# Sheet1.net
KiCad netlist of a schematic drawn in Altium Designer
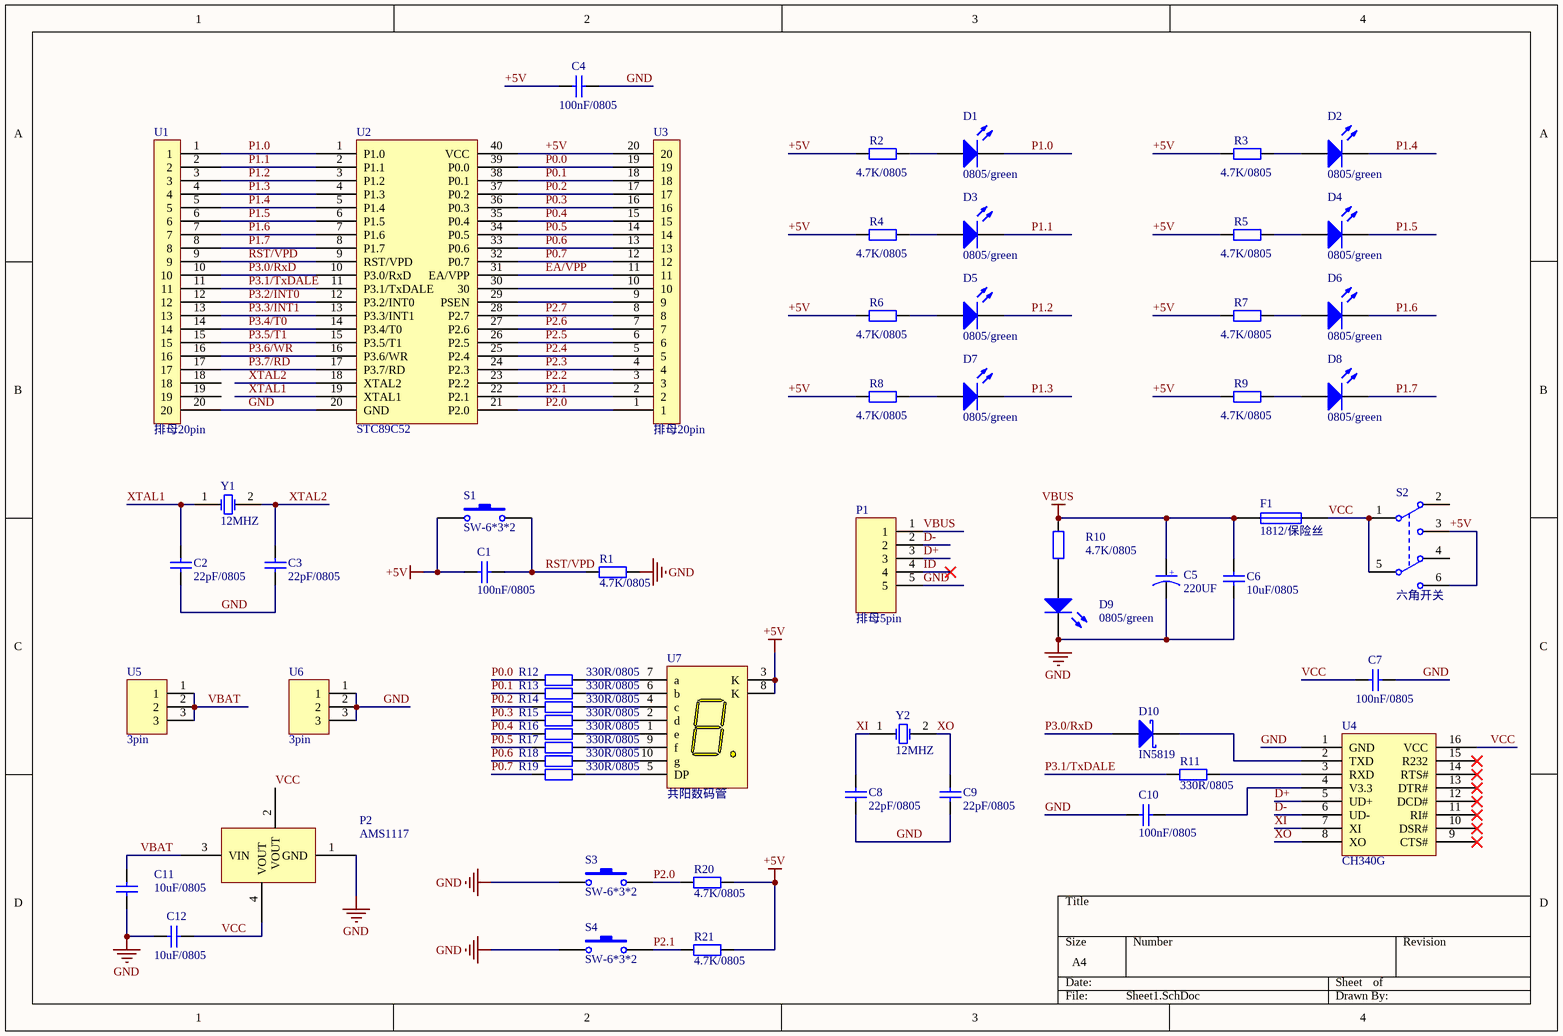
[diagram p0: Sheet1.SchDoc]

(export (version "E")
  (design (tool "Eeschema 10.0.6"))
  (components
    (comp (ref "C1")
      (value "100nF/0805")
      (footprint "C_0805")
      (description "贴片电容")
      (libsource (lib "51最小系统板") (part "Cap1_1"))
    )
    (comp (ref "C2")
      (value "22pF/0805")
      (footprint "C_0805")
      (description "贴片电容")
      (libsource (lib "51最小系统板") (part "Cap1"))
    )
    (comp (ref "C3")
      (value "22pF/0805")
      (footprint "C_0805")
      (description "贴片电容")
      (libsource (lib "51最小系统板") (part "Cap1"))
    )
    (comp (ref "C4")
      (value "100nF/0805")
      (footprint "C_0805")
      (description "贴片电容")
      (libsource (lib "51最小系统板") (part "Cap1_1"))
    )
    (comp (ref "C5")
      (value "220UF")
      (footprint "C-电解电容")
      (description "电解电容")
      (libsource (lib "51最小系统板") (part "Cap2"))
    )
    (comp (ref "C6")
      (value "10uF/0805")
      (footprint "C_0805")
      (description "贴片电容")
      (libsource (lib "51最小系统板") (part "Cap1_1"))
    )
    (comp (ref "C7")
      (value "100nF/0805")
      (footprint "C_0805")
      (description "贴片电容")
      (libsource (lib "51最小系统板") (part "Cap1_1"))
    )
    (comp (ref "C8")
      (value "22pF/0805")
      (footprint "C_0805")
      (description "贴片电容")
      (libsource (lib "51最小系统板") (part "Cap1"))
    )
    (comp (ref "C9")
      (value "22pF/0805")
      (footprint "C_0805")
      (description "贴片电容")
      (libsource (lib "51最小系统板") (part "Cap1"))
    )
    (comp (ref "C10")
      (value "100nF/0805")
      (footprint "C_0805")
      (description "贴片电容")
      (libsource (lib "51最小系统板") (part "Cap1_1"))
    )
    (comp (ref "C11")
      (value "10uF/0805")
      (footprint "C_0805")
      (description "贴片电容")
      (libsource (lib "51最小系统板") (part "Cap1"))
    )
    (comp (ref "C12")
      (value "10uF/0805")
      (footprint "C_0805")
      (description "贴片电容")
      (libsource (lib "51最小系统板") (part "Cap1"))
    )
    (comp (ref "D1")
      (value "0805/green")
      (footprint "LED_0805")
      (description "发光二极管")
      (libsource (lib "51最小系统板") (part "LED"))
    )
    (comp (ref "D2")
      (value "0805/green")
      (footprint "LED_0805")
      (description "发光二极管")
      (libsource (lib "51最小系统板") (part "LED"))
    )
    (comp (ref "D3")
      (value "0805/green")
      (footprint "LED_0805")
      (description "发光二极管")
      (libsource (lib "51最小系统板") (part "LED"))
    )
    (comp (ref "D4")
      (value "0805/green")
      (footprint "LED_0805")
      (description "发光二极管")
      (libsource (lib "51最小系统板") (part "LED"))
    )
    (comp (ref "D5")
      (value "0805/green")
      (footprint "LED_0805")
      (description "发光二极管")
      (libsource (lib "51最小系统板") (part "LED"))
    )
    (comp (ref "D6")
      (value "0805/green")
      (footprint "LED_0805")
      (description "发光二极管")
      (libsource (lib "51最小系统板") (part "LED"))
    )
    (comp (ref "D7")
      (value "0805/green")
      (footprint "LED_0805")
      (description "发光二极管")
      (libsource (lib "51最小系统板") (part "LED"))
    )
    (comp (ref "D8")
      (value "0805/green")
      (footprint "LED_0805")
      (description "发光二极管")
      (libsource (lib "51最小系统板") (part "LED"))
    )
    (comp (ref "D9")
      (value "0805/green")
      (footprint "LED_0805")
      (description "发光二极管")
      (libsource (lib "51最小系统板") (part "LED"))
    )
    (comp (ref "D10")
      (value "IN5819")
      (footprint "D-SMA")
      (description "肖特基二极管")
      (libsource (lib "51最小系统板") (part "Diode_SCHOTTKY"))
    )
    (comp (ref "F1")
      (value "1812/保险丝")
      (footprint "FUSE-1812")
      (description "贴片保险丝")
      (libsource (lib "51最小系统板") (part "FUSE"))
    )
    (comp (ref "P1") (value "排母5pin") (footprint "排母2.54-5PIN") (libsource (lib "51最小系统板") (part "排母5pin")))
    (comp (ref "P2") (value "AMS1117") (footprint "AMS1117") (libsource (lib "51最小系统板") (part "AMS1117")))
    (comp (ref "R1")
      (value "4.7K/0805")
      (footprint "R_0805")
      (description "贴片电阻")
      (libsource (lib "") (part "Res1_1_1"))
    )
    (comp (ref "R2")
      (value "4.7K/0805")
      (footprint "R_0805")
      (description "贴片电阻")
      (libsource (lib "51最小系统板") (part "Res1_1"))
    )
    (comp (ref "R3")
      (value "4.7K/0805")
      (footprint "R_0805")
      (description "贴片电阻")
      (libsource (lib "51最小系统板") (part "Res1_1"))
    )
    (comp (ref "R4")
      (value "4.7K/0805")
      (footprint "R_0805")
      (description "贴片电阻")
      (libsource (lib "51最小系统板") (part "Res1_1"))
    )
    (comp (ref "R5")
      (value "4.7K/0805")
      (footprint "R_0805")
      (description "贴片电阻")
      (libsource (lib "51最小系统板") (part "Res1_1"))
    )
    (comp (ref "R6")
      (value "4.7K/0805")
      (footprint "R_0805")
      (description "贴片电阻")
      (libsource (lib "51最小系统板") (part "Res1_1"))
    )
    (comp (ref "R7")
      (value "4.7K/0805")
      (footprint "R_0805")
      (description "贴片电阻")
      (libsource (lib "51最小系统板") (part "Res1_1"))
    )
    (comp (ref "R8")
      (value "4.7K/0805")
      (footprint "R_0805")
      (description "贴片电阻")
      (libsource (lib "51最小系统板") (part "Res1_1"))
    )
    (comp (ref "R9")
      (value "4.7K/0805")
      (footprint "R_0805")
      (description "贴片电阻")
      (libsource (lib "51最小系统板") (part "Res1_1"))
    )
    (comp (ref "R10")
      (value "4.7K/0805")
      (footprint "R_0805")
      (description "贴片电阻")
      (libsource (lib "") (part "Res1_1_2"))
    )
    (comp (ref "R11")
      (value "330R/0805")
      (footprint "R_0805")
      (description "贴片电阻")
      (libsource (lib "51最小系统板") (part "Res1_1"))
    )
    (comp (ref "R12")
      (value "330R/0805")
      (footprint "R_0805")
      (description "贴片电阻")
      (libsource (lib "") (part "Res1_1_1"))
    )
    (comp (ref "R13")
      (value "330R/0805")
      (footprint "R_0805")
      (description "贴片电阻")
      (libsource (lib "") (part "Res1_1_1"))
    )
    (comp (ref "R14")
      (value "330R/0805")
      (footprint "R_0805")
      (description "贴片电阻")
      (libsource (lib "") (part "Res1_1_1"))
    )
    (comp (ref "R15")
      (value "330R/0805")
      (footprint "R_0805")
      (description "贴片电阻")
      (libsource (lib "") (part "Res1_1_1"))
    )
    (comp (ref "R16")
      (value "330R/0805")
      (footprint "R_0805")
      (description "贴片电阻")
      (libsource (lib "") (part "Res1_1_1"))
    )
    (comp (ref "R17")
      (value "330R/0805")
      (footprint "R_0805")
      (description "贴片电阻")
      (libsource (lib "") (part "Res1_1_1"))
    )
    (comp (ref "R18")
      (value "330R/0805")
      (footprint "R_0805")
      (description "贴片电阻")
      (libsource (lib "") (part "Res1_1_1"))
    )
    (comp (ref "R19")
      (value "330R/0805")
      (footprint "R_0805")
      (description "贴片电阻")
      (libsource (lib "") (part "Res1_1_1"))
    )
    (comp (ref "R20")
      (value "4.7K/0805")
      (footprint "R_0805")
      (description "贴片电阻")
      (libsource (lib "") (part "Res1_1_1"))
    )
    (comp (ref "R21")
      (value "4.7K/0805")
      (footprint "R_0805")
      (description "贴片电阻")
      (libsource (lib "") (part "Res1_1_1"))
    )
    (comp (ref "S1")
      (value "SW-6*3*2")
      (footprint "SW-3*6*2.5")
      (libsource (lib "51最小系统板") (part "SW-6*3*2"))
    )
    (comp (ref "S2") (value "六角开关") (footprint "六角开关7X7") (libsource (lib "51最小系统板") (part "六角开关")))
    (comp (ref "S3")
      (value "SW-6*3*2")
      (footprint "SW-3*6*2.5")
      (libsource (lib "51最小系统板") (part "SW-6*3*2"))
    )
    (comp (ref "S4")
      (value "SW-6*3*2")
      (footprint "SW-3*6*2.5")
      (libsource (lib "51最小系统板") (part "SW-6*3*2"))
    )
    (comp (ref "U1") (value "排母20pin") (footprint "20PIN-2.54") (libsource (lib "51最小系统板") (part "排母20pin")))
    (comp (ref "U2") (value "STC89C52") (footprint "STC89C51") (libsource (lib "51最小系统板") (part "STC89C52")))
    (comp (ref "U3") (value "排母20pin") (footprint "20PIN-2.54") (libsource (lib "") (part "排母20pin_1")))
    (comp (ref "U4") (value "CH340G") (footprint "CH340G") (libsource (lib "51最小系统板") (part "CH340G")))
    (comp (ref "U5") (value "3pin") (footprint "3PIN-2.54") (libsource (lib "51最小系统板") (part "3pin")))
    (comp (ref "U6") (value "3pin") (footprint "3PIN-2.54") (libsource (lib "51最小系统板") (part "3pin")))
    (comp (ref "U7") (value "共阳数码管") (footprint "数码管") (libsource (lib "51最小系统板") (part "共阳数码管")))
    (comp (ref "Y1")
      (value "12MHZ")
      (footprint "HC495")
      (description "二脚无源晶振")
      (libsource (lib "51最小系统板") (part "XTAL_2P"))
    )
    (comp (ref "Y2")
      (value "12MHZ")
      (footprint "HC495")
      (description "二脚无源晶振")
      (libsource (lib "51最小系统板") (part "XTAL_2P"))
    )
  )
  (nets
    (net (code "1") (name "+5V") (class "Default")
      (node (ref "C1") (pin "2") (pinfunction "2_2") (pintype "passive"))
      (node (ref "C4") (pin "2") (pinfunction "2_2") (pintype "passive"))
      (node (ref "R2") (pin "1") (pinfunction "1_1") (pintype "passive"))
      (node (ref "R20") (pin "1") (pinfunction "1_1") (pintype "passive"))
      (node (ref "R21") (pin "1") (pinfunction "1_1") (pintype "passive"))
      (node (ref "R3") (pin "1") (pinfunction "1_1") (pintype "passive"))
      (node (ref "R4") (pin "1") (pinfunction "1_1") (pintype "passive"))
      (node (ref "R5") (pin "1") (pinfunction "1_1") (pintype "passive"))
      (node (ref "R6") (pin "1") (pinfunction "1_1") (pintype "passive"))
      (node (ref "R7") (pin "1") (pinfunction "1_1") (pintype "passive"))
      (node (ref "R8") (pin "1") (pinfunction "1_1") (pintype "passive"))
      (node (ref "R9") (pin "1") (pinfunction "1_1") (pintype "passive"))
      (node (ref "S1") (pin "1") (pinfunction "1_1") (pintype "passive"))
      (node (ref "S2") (pin "3") (pinfunction "NO1_3") (pintype "passive"))
      (node (ref "S2") (pin "6") (pinfunction "NO2_6") (pintype "passive"))
      (node (ref "U2") (pin "40") (pinfunction "VCC_40") (pintype "passive"))
      (node (ref "U3") (pin "20") (pinfunction "20_20") (pintype "passive"))
      (node (ref "U7") (pin "3") (pinfunction "K_3") (pintype "passive"))
      (node (ref "U7") (pin "8") (pinfunction "K_8") (pintype "passive"))
    )
    (net (code "2") (name "/D+") (class "Default")
      (node (ref "P1") (pin "3") (pinfunction "3_3") (pintype "passive"))
      (node (ref "U4") (pin "5") (pinfunction "UD+_5") (pintype "passive"))
    )
    (net (code "3") (name "/D-") (class "Default")
      (node (ref "P1") (pin "2") (pinfunction "2_2") (pintype "passive"))
      (node (ref "U4") (pin "6") (pinfunction "UD-_6") (pintype "passive"))
    )
    (net (code "4") (name "/EA{slash}VPP") (class "Default")
      (node (ref "U2") (pin "31") (pinfunction "EA/VPP_31") (pintype "passive"))
      (node (ref "U3") (pin "11") (pinfunction "11_11") (pintype "passive"))
    )
    (net (code "5") (name "/ID") (class "Default")
      (node (ref "P1") (pin "4") (pinfunction "4_4") (pintype "passive+no_connect"))
    )
    (net (code "6") (name "/P0.0") (class "Default")
      (node (ref "R12") (pin "2") (pinfunction "2_2") (pintype "passive"))
      (node (ref "U2") (pin "39") (pinfunction "P0.0_39") (pintype "passive"))
      (node (ref "U3") (pin "19") (pinfunction "19_19") (pintype "passive"))
    )
    (net (code "7") (name "/P0.1") (class "Default")
      (node (ref "R13") (pin "2") (pinfunction "2_2") (pintype "passive"))
      (node (ref "U2") (pin "38") (pinfunction "P0.1_38") (pintype "passive"))
      (node (ref "U3") (pin "18") (pinfunction "18_18") (pintype "passive"))
    )
    (net (code "8") (name "/P0.2") (class "Default")
      (node (ref "R14") (pin "2") (pinfunction "2_2") (pintype "passive"))
      (node (ref "U2") (pin "37") (pinfunction "P0.2_37") (pintype "passive"))
      (node (ref "U3") (pin "17") (pinfunction "17_17") (pintype "passive"))
    )
    (net (code "9") (name "/P0.3") (class "Default")
      (node (ref "R15") (pin "2") (pinfunction "2_2") (pintype "passive"))
      (node (ref "U2") (pin "36") (pinfunction "P0.3_36") (pintype "passive"))
      (node (ref "U3") (pin "16") (pinfunction "16_16") (pintype "passive"))
    )
    (net (code "10") (name "/P0.4") (class "Default")
      (node (ref "R16") (pin "2") (pinfunction "2_2") (pintype "passive"))
      (node (ref "U2") (pin "35") (pinfunction "P0.4_35") (pintype "passive"))
      (node (ref "U3") (pin "15") (pinfunction "15_15") (pintype "passive"))
    )
    (net (code "11") (name "/P0.5") (class "Default")
      (node (ref "R17") (pin "2") (pinfunction "2_2") (pintype "passive"))
      (node (ref "U2") (pin "34") (pinfunction "P0.5_34") (pintype "passive"))
      (node (ref "U3") (pin "14") (pinfunction "14_14") (pintype "passive"))
    )
    (net (code "12") (name "/P0.6") (class "Default")
      (node (ref "R18") (pin "2") (pinfunction "2_2") (pintype "passive"))
      (node (ref "U2") (pin "33") (pinfunction "P0.6_33") (pintype "passive"))
      (node (ref "U3") (pin "13") (pinfunction "13_13") (pintype "passive"))
    )
    (net (code "13") (name "/P0.7") (class "Default")
      (node (ref "R19") (pin "2") (pinfunction "2_2") (pintype "passive"))
      (node (ref "U2") (pin "32") (pinfunction "P0.7_32") (pintype "passive"))
      (node (ref "U3") (pin "12") (pinfunction "12_12") (pintype "passive"))
    )
    (net (code "14") (name "/P1.0") (class "Default")
      (node (ref "D1") (pin "2") (pinfunction "2_2") (pintype "passive"))
      (node (ref "U1") (pin "1") (pinfunction "1_1") (pintype "passive"))
      (node (ref "U2") (pin "1") (pinfunction "P1.0_1") (pintype "passive"))
    )
    (net (code "15") (name "/P1.1") (class "Default")
      (node (ref "D3") (pin "2") (pinfunction "2_2") (pintype "passive"))
      (node (ref "U1") (pin "2") (pinfunction "2_2") (pintype "passive"))
      (node (ref "U2") (pin "2") (pinfunction "P1.1_2") (pintype "passive"))
    )
    (net (code "16") (name "/P1.2") (class "Default")
      (node (ref "D5") (pin "2") (pinfunction "2_2") (pintype "passive"))
      (node (ref "U1") (pin "3") (pinfunction "3_3") (pintype "passive"))
      (node (ref "U2") (pin "3") (pinfunction "P1.2_3") (pintype "passive"))
    )
    (net (code "17") (name "/P1.3") (class "Default")
      (node (ref "D7") (pin "2") (pinfunction "2_2") (pintype "passive"))
      (node (ref "U1") (pin "4") (pinfunction "4_4") (pintype "passive"))
      (node (ref "U2") (pin "4") (pinfunction "P1.3_4") (pintype "passive"))
    )
    (net (code "18") (name "/P1.4") (class "Default")
      (node (ref "D2") (pin "2") (pinfunction "2_2") (pintype "passive"))
      (node (ref "U1") (pin "5") (pinfunction "5_5") (pintype "passive"))
      (node (ref "U2") (pin "5") (pinfunction "P1.4_5") (pintype "passive"))
    )
    (net (code "19") (name "/P1.5") (class "Default")
      (node (ref "D4") (pin "2") (pinfunction "2_2") (pintype "passive"))
      (node (ref "U1") (pin "6") (pinfunction "6_6") (pintype "passive"))
      (node (ref "U2") (pin "6") (pinfunction "P1.5_6") (pintype "passive"))
    )
    (net (code "20") (name "/P1.6") (class "Default")
      (node (ref "D6") (pin "2") (pinfunction "2_2") (pintype "passive"))
      (node (ref "U1") (pin "7") (pinfunction "7_7") (pintype "passive"))
      (node (ref "U2") (pin "7") (pinfunction "P1.6_7") (pintype "passive"))
    )
    (net (code "21") (name "/P1.7") (class "Default")
      (node (ref "D8") (pin "2") (pinfunction "2_2") (pintype "passive"))
      (node (ref "U1") (pin "8") (pinfunction "8_8") (pintype "passive"))
      (node (ref "U2") (pin "8") (pinfunction "P1.7_8") (pintype "passive"))
    )
    (net (code "22") (name "/P2.0") (class "Default")
      (node (ref "R20") (pin "2") (pinfunction "2_2") (pintype "passive"))
      (node (ref "S3") (pin "2") (pinfunction "2_2") (pintype "passive"))
      (node (ref "U2") (pin "21") (pinfunction "P2.0_21") (pintype "passive"))
      (node (ref "U3") (pin "1") (pinfunction "1_1") (pintype "passive"))
    )
    (net (code "23") (name "/P2.1") (class "Default")
      (node (ref "R21") (pin "2") (pinfunction "2_2") (pintype "passive"))
      (node (ref "S4") (pin "2") (pinfunction "2_2") (pintype "passive"))
      (node (ref "U2") (pin "22") (pinfunction "P2.1_22") (pintype "passive"))
      (node (ref "U3") (pin "2") (pinfunction "2_2") (pintype "passive"))
    )
    (net (code "24") (name "/P2.2") (class "Default")
      (node (ref "U2") (pin "23") (pinfunction "P2.2_23") (pintype "passive"))
      (node (ref "U3") (pin "3") (pinfunction "3_3") (pintype "passive"))
    )
    (net (code "25") (name "/P2.3") (class "Default")
      (node (ref "U2") (pin "24") (pinfunction "P2.3_24") (pintype "passive"))
      (node (ref "U3") (pin "4") (pinfunction "4_4") (pintype "passive"))
    )
    (net (code "26") (name "/P2.4") (class "Default")
      (node (ref "U2") (pin "25") (pinfunction "P2.4_25") (pintype "passive"))
      (node (ref "U3") (pin "5") (pinfunction "5_5") (pintype "passive"))
    )
    (net (code "27") (name "/P2.5") (class "Default")
      (node (ref "U2") (pin "26") (pinfunction "P2.5_26") (pintype "passive"))
      (node (ref "U3") (pin "6") (pinfunction "6_6") (pintype "passive"))
    )
    (net (code "28") (name "/P2.6") (class "Default")
      (node (ref "U2") (pin "27") (pinfunction "P2.6_27") (pintype "passive"))
      (node (ref "U3") (pin "7") (pinfunction "7_7") (pintype "passive"))
    )
    (net (code "29") (name "/P2.7") (class "Default")
      (node (ref "U2") (pin "28") (pinfunction "P2.7_28") (pintype "passive"))
      (node (ref "U3") (pin "8") (pinfunction "8_8") (pintype "passive"))
    )
    (net (code "30") (name "/P3.0{slash}RxD") (class "Default")
      (node (ref "D10") (pin "2") (pinfunction "A_2") (pintype "passive"))
      (node (ref "U1") (pin "10") (pinfunction "10_10") (pintype "passive"))
      (node (ref "U2") (pin "10") (pinfunction "P3.0/RxD_10") (pintype "passive"))
    )
    (net (code "31") (name "/P3.1{slash}TxDALE") (class "Default")
      (node (ref "R11") (pin "1") (pinfunction "1_1") (pintype "passive"))
      (node (ref "U1") (pin "11") (pinfunction "11_11") (pintype "passive"))
      (node (ref "U2") (pin "11") (pinfunction "P3.1/TxDALE_11") (pintype "passive"))
    )
    (net (code "32") (name "/P3.2{slash}INT0") (class "Default")
      (node (ref "U1") (pin "12") (pinfunction "12_12") (pintype "passive"))
      (node (ref "U2") (pin "12") (pinfunction "P3.2/INT0_12") (pintype "passive"))
    )
    (net (code "33") (name "/P3.3{slash}INT1") (class "Default")
      (node (ref "U1") (pin "13") (pinfunction "13_13") (pintype "passive"))
      (node (ref "U2") (pin "13") (pinfunction "P3.3/INT1_13") (pintype "passive"))
    )
    (net (code "34") (name "/P3.4{slash}T0") (class "Default")
      (node (ref "U1") (pin "14") (pinfunction "14_14") (pintype "passive"))
      (node (ref "U2") (pin "14") (pinfunction "P3.4/T0_14") (pintype "passive"))
    )
    (net (code "35") (name "/P3.5{slash}T1") (class "Default")
      (node (ref "U1") (pin "15") (pinfunction "15_15") (pintype "passive"))
      (node (ref "U2") (pin "15") (pinfunction "P3.5/T1_15") (pintype "passive"))
    )
    (net (code "36") (name "/P3.6{slash}WR") (class "Default")
      (node (ref "U1") (pin "16") (pinfunction "16_16") (pintype "passive"))
      (node (ref "U2") (pin "16") (pinfunction "P3.6/WR_16") (pintype "passive"))
    )
    (net (code "37") (name "/P3.7{slash}RD") (class "Default")
      (node (ref "U1") (pin "17") (pinfunction "17_17") (pintype "passive"))
      (node (ref "U2") (pin "17") (pinfunction "P3.7/RD_17") (pintype "passive"))
    )
    (net (code "38") (name "/RST{slash}VPD") (class "Default")
      (node (ref "C1") (pin "1") (pinfunction "1_1") (pintype "passive"))
      (node (ref "R1") (pin "2") (pinfunction "2_2") (pintype "passive"))
      (node (ref "S1") (pin "2") (pinfunction "2_2") (pintype "passive"))
      (node (ref "U1") (pin "9") (pinfunction "9_9") (pintype "passive"))
      (node (ref "U2") (pin "9") (pinfunction "RST/VPD_9") (pintype "passive"))
    )
    (net (code "39") (name "/VBAT") (class "Default")
      (node (ref "C11") (pin "2") (pinfunction "2_2") (pintype "passive"))
      (node (ref "P2") (pin "3") (pinfunction "VIN_3") (pintype "passive"))
      (node (ref "U5") (pin "1") (pinfunction "1_1") (pintype "passive"))
      (node (ref "U5") (pin "2") (pinfunction "2_2") (pintype "passive"))
      (node (ref "U5") (pin "3") (pinfunction "3_3") (pintype "passive"))
    )
    (net (code "40") (name "/VCC") (class "Default")
      (node (ref "C12") (pin "1") (pinfunction "1_1") (pintype "passive"))
      (node (ref "C7") (pin "2") (pinfunction "2_2") (pintype "passive"))
      (node (ref "F1") (pin "1") (pinfunction "1_1") (pintype "passive"))
      (node (ref "P2") (pin "2") (pinfunction "VOUT_2") (pintype "passive"))
      (node (ref "P2") (pin "4") (pinfunction "VOUT_4") (pintype "passive"))
      (node (ref "S2") (pin "1") (pinfunction "COMMON1_1") (pintype "passive"))
      (node (ref "S2") (pin "5") (pinfunction "COMMON2_5") (pintype "passive"))
      (node (ref "U4") (pin "16") (pinfunction "VCC_16") (pintype "passive"))
    )
    (net (code "41") (name "/XI") (class "Default")
      (node (ref "C8") (pin "2") (pinfunction "2_2") (pintype "passive"))
      (node (ref "U4") (pin "7") (pinfunction "XI_7") (pintype "passive"))
      (node (ref "Y2") (pin "1") (pinfunction "OSC1_1") (pintype "passive"))
    )
    (net (code "42") (name "/XO") (class "Default")
      (node (ref "C9") (pin "2") (pinfunction "2_2") (pintype "passive"))
      (node (ref "U4") (pin "8") (pinfunction "XO_8") (pintype "passive"))
      (node (ref "Y2") (pin "2") (pinfunction "OSC2_2") (pintype "passive"))
    )
    (net (code "43") (name "/XTAL1") (class "Default")
      (node (ref "C2") (pin "2") (pinfunction "2_2") (pintype "passive"))
      (node (ref "U2") (pin "19") (pinfunction "XTAL1_19") (pintype "passive"))
      (node (ref "Y1") (pin "1") (pinfunction "OSC1_1") (pintype "passive"))
    )
    (net (code "44") (name "/XTAL2") (class "Default")
      (node (ref "C3") (pin "2") (pinfunction "2_2") (pintype "passive"))
      (node (ref "U2") (pin "18") (pinfunction "XTAL2_18") (pintype "passive"))
      (node (ref "Y1") (pin "2") (pinfunction "OSC2_2") (pintype "passive"))
    )
    (net (code "45") (name "GND") (class "Default")
      (node (ref "C10") (pin "1") (pinfunction "1_1") (pintype "passive"))
      (node (ref "C11") (pin "1") (pinfunction "1_1") (pintype "passive"))
      (node (ref "C12") (pin "2") (pinfunction "2_2") (pintype "passive"))
      (node (ref "C2") (pin "1") (pinfunction "1_1") (pintype "passive"))
      (node (ref "C3") (pin "1") (pinfunction "1_1") (pintype "passive"))
      (node (ref "C4") (pin "1") (pinfunction "1_1") (pintype "passive"))
      (node (ref "C5") (pin "2") (pinfunction "15_2") (pintype "passive"))
      (node (ref "C6") (pin "2") (pinfunction "2_2") (pintype "passive"))
      (node (ref "C7") (pin "1") (pinfunction "1_1") (pintype "passive"))
      (node (ref "C8") (pin "1") (pinfunction "1_1") (pintype "passive"))
      (node (ref "C9") (pin "1") (pinfunction "1_1") (pintype "passive"))
      (node (ref "D9") (pin "2") (pinfunction "2_2") (pintype "passive"))
      (node (ref "P1") (pin "5") (pinfunction "5_5") (pintype "passive"))
      (node (ref "P2") (pin "1") (pinfunction "GND_1") (pintype "passive"))
      (node (ref "R1") (pin "1") (pinfunction "1_1") (pintype "passive"))
      (node (ref "S3") (pin "1") (pinfunction "1_1") (pintype "passive"))
      (node (ref "S4") (pin "1") (pinfunction "1_1") (pintype "passive"))
      (node (ref "U1") (pin "20") (pinfunction "20_20") (pintype "passive"))
      (node (ref "U2") (pin "20") (pinfunction "GND_20") (pintype "passive"))
      (node (ref "U4") (pin "1") (pinfunction "GND_1") (pintype "passive"))
      (node (ref "U6") (pin "1") (pinfunction "1_1") (pintype "passive"))
      (node (ref "U6") (pin "2") (pinfunction "2_2") (pintype "passive"))
      (node (ref "U6") (pin "3") (pinfunction "3_3") (pintype "passive"))
    )
    (net (code "46") (name "Net-(D1-A1)") (class "Default")
      (node (ref "D1") (pin "1") (pinfunction "A1_1") (pintype "passive"))
      (node (ref "R2") (pin "2") (pinfunction "2_2") (pintype "passive"))
    )
    (net (code "47") (name "Net-(D2-A1)") (class "Default")
      (node (ref "D2") (pin "1") (pinfunction "A1_1") (pintype "passive"))
      (node (ref "R3") (pin "2") (pinfunction "2_2") (pintype "passive"))
    )
    (net (code "48") (name "Net-(D3-A1)") (class "Default")
      (node (ref "D3") (pin "1") (pinfunction "A1_1") (pintype "passive"))
      (node (ref "R4") (pin "2") (pinfunction "2_2") (pintype "passive"))
    )
    (net (code "49") (name "Net-(D4-A1)") (class "Default")
      (node (ref "D4") (pin "1") (pinfunction "A1_1") (pintype "passive"))
      (node (ref "R5") (pin "2") (pinfunction "2_2") (pintype "passive"))
    )
    (net (code "50") (name "Net-(D5-A1)") (class "Default")
      (node (ref "D5") (pin "1") (pinfunction "A1_1") (pintype "passive"))
      (node (ref "R6") (pin "2") (pinfunction "2_2") (pintype "passive"))
    )
    (net (code "51") (name "Net-(D6-A1)") (class "Default")
      (node (ref "D6") (pin "1") (pinfunction "A1_1") (pintype "passive"))
      (node (ref "R7") (pin "2") (pinfunction "2_2") (pintype "passive"))
    )
    (net (code "52") (name "Net-(D7-A1)") (class "Default")
      (node (ref "D7") (pin "1") (pinfunction "A1_1") (pintype "passive"))
      (node (ref "R8") (pin "2") (pinfunction "2_2") (pintype "passive"))
    )
    (net (code "53") (name "Net-(D8-A1)") (class "Default")
      (node (ref "D8") (pin "1") (pinfunction "A1_1") (pintype "passive"))
      (node (ref "R9") (pin "2") (pinfunction "2_2") (pintype "passive"))
    )
    (net (code "54") (name "Net-(D9-A1)") (class "Default")
      (node (ref "D9") (pin "1") (pinfunction "A1_1") (pintype "passive"))
      (node (ref "R10") (pin "2") (pinfunction "2_2") (pintype "passive"))
    )
    (net (code "55") (name "Net-(D10-K)") (class "Default")
      (node (ref "D10") (pin "1") (pinfunction "K_1") (pintype "passive"))
      (node (ref "U4") (pin "2") (pinfunction "TXD_2") (pintype "passive"))
    )
    (net (code "56") (name "Net-(U2-PSEN)") (class "Default")
      (node (ref "U2") (pin "29") (pinfunction "PSEN_29") (pintype "passive"))
      (node (ref "U3") (pin "9") (pinfunction "9_9") (pintype "passive"))
    )
    (net (code "57") (name "Net-(U2-Pad30)") (class "Default")
      (node (ref "U2") (pin "30") (pinfunction "30_30") (pintype "passive"))
      (node (ref "U3") (pin "10") (pinfunction "10_10") (pintype "passive"))
    )
    (net (code "58") (name "Net-(U4-RXD)") (class "Default")
      (node (ref "R11") (pin "2") (pinfunction "2_2") (pintype "passive"))
      (node (ref "U4") (pin "3") (pinfunction "RXD_3") (pintype "passive"))
    )
    (net (code "59") (name "Net-(U4-V3.3)") (class "Default")
      (node (ref "C10") (pin "2") (pinfunction "2_2") (pintype "passive"))
      (node (ref "U4") (pin "4") (pinfunction "V3.3_4") (pintype "passive"))
    )
    (net (code "60") (name "Net-(U7-DP)") (class "Default")
      (node (ref "R19") (pin "1") (pinfunction "1_1") (pintype "passive"))
      (node (ref "U7") (pin "5") (pinfunction "DP_5") (pintype "passive"))
    )
    (net (code "61") (name "Net-(U7-a)") (class "Default")
      (node (ref "R12") (pin "1") (pinfunction "1_1") (pintype "passive"))
      (node (ref "U7") (pin "7") (pinfunction "a_7") (pintype "passive"))
    )
    (net (code "62") (name "Net-(U7-b)") (class "Default")
      (node (ref "R13") (pin "1") (pinfunction "1_1") (pintype "passive"))
      (node (ref "U7") (pin "6") (pinfunction "b_6") (pintype "passive"))
    )
    (net (code "63") (name "Net-(U7-c)") (class "Default")
      (node (ref "R14") (pin "1") (pinfunction "1_1") (pintype "passive"))
      (node (ref "U7") (pin "4") (pinfunction "c_4") (pintype "passive"))
    )
    (net (code "64") (name "Net-(U7-d)") (class "Default")
      (node (ref "R15") (pin "1") (pinfunction "1_1") (pintype "passive"))
      (node (ref "U7") (pin "2") (pinfunction "d_2") (pintype "passive"))
    )
    (net (code "65") (name "Net-(U7-e)") (class "Default")
      (node (ref "R16") (pin "1") (pinfunction "1_1") (pintype "passive"))
      (node (ref "U7") (pin "1") (pinfunction "e_1") (pintype "passive"))
    )
    (net (code "66") (name "Net-(U7-f)") (class "Default")
      (node (ref "R17") (pin "1") (pinfunction "1_1") (pintype "passive"))
      (node (ref "U7") (pin "9") (pinfunction "f_9") (pintype "passive"))
    )
    (net (code "67") (name "Net-(U7-g)") (class "Default")
      (node (ref "R18") (pin "1") (pinfunction "1_1") (pintype "passive"))
      (node (ref "U7") (pin "10") (pinfunction "g_10") (pintype "passive"))
    )
    (net (code "68") (name "VBUS") (class "Default")
      (node (ref "C5") (pin "1") (pinfunction "A_1") (pintype "passive"))
      (node (ref "C6") (pin "1") (pinfunction "1_1") (pintype "passive"))
      (node (ref "F1") (pin "2") (pinfunction "2_2") (pintype "passive"))
      (node (ref "P1") (pin "1") (pinfunction "1_1") (pintype "passive"))
      (node (ref "R10") (pin "1") (pinfunction "1_1") (pintype "passive"))
    )
    (net (code "69") (name "unconnected-(S2-NC1-Pad2)") (class "Default")
      (node (ref "S2") (pin "2") (pinfunction "NC1_2") (pintype "passive"))
    )
    (net (code "70") (name "unconnected-(S2-NC2-Pad4)") (class "Default")
      (node (ref "S2") (pin "4") (pinfunction "NC2_4") (pintype "passive"))
    )
    (net (code "71") (name "unconnected-(U1-Pad18)") (class "Default")
      (node (ref "U1") (pin "18") (pinfunction "18_18") (pintype "passive"))
    )
    (net (code "72") (name "unconnected-(U1-Pad19)") (class "Default")
      (node (ref "U1") (pin "19") (pinfunction "19_19") (pintype "passive"))
    )
    (net (code "73") (name "unconnected-(U4-CTS#-Pad9)") (class "Default")
      (node (ref "U4") (pin "9") (pinfunction "CTS#_9") (pintype "passive+no_connect"))
    )
    (net (code "74") (name "unconnected-(U4-DCD#-Pad12)") (class "Default")
      (node (ref "U4") (pin "12") (pinfunction "DCD#_12") (pintype "passive+no_connect"))
    )
    (net (code "75") (name "unconnected-(U4-DSR#-Pad10)") (class "Default")
      (node (ref "U4") (pin "10") (pinfunction "DSR#_10") (pintype "passive+no_connect"))
    )
    (net (code "76") (name "unconnected-(U4-DTR#-Pad13)") (class "Default")
      (node (ref "U4") (pin "13") (pinfunction "DTR#_13") (pintype "passive+no_connect"))
    )
    (net (code "77") (name "unconnected-(U4-R232-Pad15)") (class "Default")
      (node (ref "U4") (pin "15") (pinfunction "R232_15") (pintype "passive+no_connect"))
    )
    (net (code "78") (name "unconnected-(U4-RI#-Pad11)") (class "Default")
      (node (ref "U4") (pin "11") (pinfunction "RI#_11") (pintype "passive+no_connect"))
    )
    (net (code "79") (name "unconnected-(U4-RTS#-Pad14)") (class "Default")
      (node (ref "U4") (pin "14") (pinfunction "RTS#_14") (pintype "passive+no_connect"))
    )
  )
)
